# GPI.net
KiCad netlist of a schematic drawn in Altium Designer
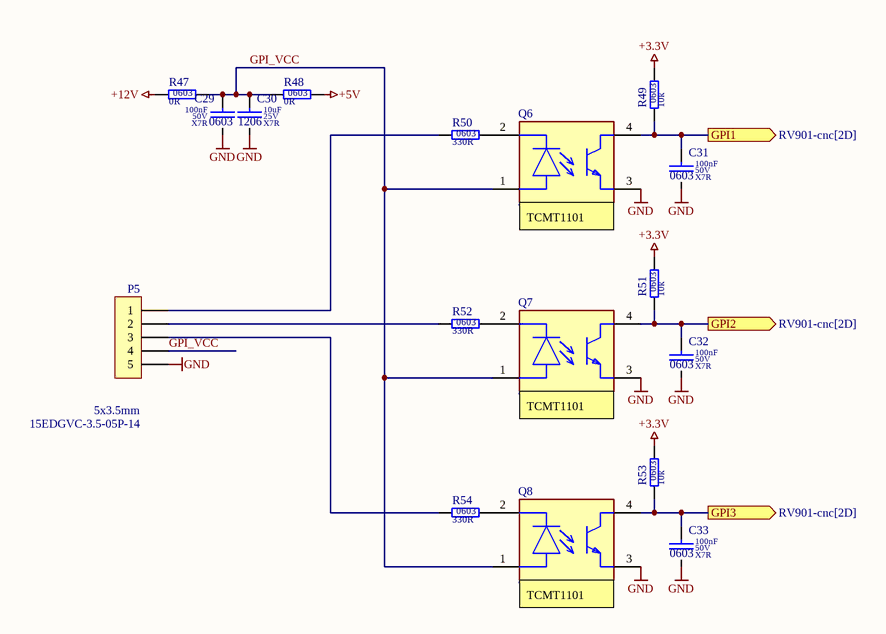
[diagram p0: GPI.SchDoc]

(export (version "E")
  (design (tool "Eeschema 10.0.6"))
  (components
    (comp (ref "C29")
      (value "100nF")
      (footprint "C_0603_1608")
      (description "Capacitor")
      (fields
        (field (name "DIELECTRIC") "X7R")
        (field (name "VOLTAGE") "50V")
        (field (name "SCH_FOOTPRINT") "0603")
        (field (name "PART NUMBER") "C_100nF_50V_X7R_0603_5")
        (field (name "MANUFACTURER") "Samsung")
      )
      (libsource (lib "Library") (part "C"))
    )
    (comp (ref "C30")
      (value "10uF")
      (footprint "C_1206_3216")
      (description "Capacitor")
      (fields
        (field (name "DIELECTRIC") "X7R")
        (field (name "VOLTAGE") "25V")
        (field (name "SCH_FOOTPRINT") "1206")
        (field (name "PART NUMBER") "C_10uF_25V_X7R_1206_10")
        (field (name "MANUFACTURER") "Samsung")
      )
      (libsource (lib "Library") (part "C"))
    )
    (comp (ref "C31")
      (value "100nF")
      (footprint "C_0603_1608")
      (description "Capacitor")
      (fields
        (field (name "DIELECTRIC") "X7R")
        (field (name "VOLTAGE") "50V")
        (field (name "SCH_FOOTPRINT") "0603")
        (field (name "PART NUMBER") "C_100nF_50V_X7R_0603_5")
        (field (name "MANUFACTURER") "Samsung")
      )
      (libsource (lib "Library") (part "C"))
    )
    (comp (ref "C32")
      (value "100nF")
      (footprint "C_0603_1608")
      (description "Capacitor")
      (fields
        (field (name "DIELECTRIC") "X7R")
        (field (name "VOLTAGE") "50V")
        (field (name "SCH_FOOTPRINT") "0603")
        (field (name "PART NUMBER") "C_100nF_50V_X7R_0603_5")
        (field (name "MANUFACTURER") "Samsung")
      )
      (libsource (lib "Library") (part "C"))
    )
    (comp (ref "C33")
      (value "100nF")
      (footprint "C_0603_1608")
      (description "Capacitor")
      (fields
        (field (name "DIELECTRIC") "X7R")
        (field (name "VOLTAGE") "50V")
        (field (name "SCH_FOOTPRINT") "0603")
        (field (name "PART NUMBER") "C_100nF_50V_X7R_0603_5")
        (field (name "MANUFACTURER") "Samsung")
      )
      (libsource (lib "Library") (part "C"))
    )
    (comp (ref "P5")
      (value "15EDGVC-3.5-05P-14")
      (footprint "P_15EDGVC-3.5-05P")
      (description "Pin Header")
      (fields
        (field (name "SCH_FOOTPRINT") "5x3.5mm")
        (field (name "PART NUMBER") "P_15EDGVC-3.5-05P-14")
        (field (name "MANUFACTURER") "DEGSON ELECTRONICS")
      )
      (libsource (lib "Library") (part "P_HEADER_1x5"))
    )
    (comp (ref "Q6")
      (value "TCMT1106")
      (footprint "FP-TCMT1106-MFG")
      (fields (field (name "VOLTAGE") "6V"))
      (libsource (lib "Altium Content Vault") (part "e07288ace2826ef443abdfb88e741da"))
    )
    (comp (ref "Q7")
      (value "TCMT1106")
      (footprint "FP-TCMT1106-MFG")
      (fields (field (name "VOLTAGE") "6V"))
      (libsource (lib "Altium Content Vault") (part "e07288ace2826ef443abdfb88e741da"))
    )
    (comp (ref "Q8")
      (value "TCMT1106")
      (footprint "FP-TCMT1106-MFG")
      (fields (field (name "VOLTAGE") "6V"))
      (libsource (lib "Altium Content Vault") (part "e07288ace2826ef443abdfb88e741da"))
    )
    (comp (ref "R47")
      (value "0R")
      (footprint "R_0603_1608")
      (fields
        (field (name "SCH_FOOTPRINT") "0603")
        (field (name "PART NUMBER") "R_0R_0603_1")
        (field (name "VOLTAGE") "75V")
        (field (name "POWER") "100mW")
      )
      (libsource (lib "Library") (part "R"))
    )
    (comp (ref "R48")
      (value "0R")
      (footprint "R_0603_1608")
      (fields
        (field (name "SCH_FOOTPRINT") "0603")
        (field (name "PART NUMBER") "R_0R_0603_1")
        (field (name "VOLTAGE") "75V")
        (field (name "POWER") "100mW")
      )
      (libsource (lib "Library") (part "R"))
    )
    (comp (ref "R49")
      (value "10k")
      (footprint "R_0603_1608")
      (fields
        (field (name "SCH_FOOTPRINT") "0603")
        (field (name "PART NUMBER") "R_10k_0603_1_AECQ0")
        (field (name "VOLTAGE") "75V")
        (field (name "POWER") "100mW")
      )
      (libsource (lib "Library") (part "R"))
    )
    (comp (ref "R50")
      (value "330R")
      (footprint "R_0603_1608")
      (fields
        (field (name "SCH_FOOTPRINT") "0603")
        (field (name "PART NUMBER") "R_330R_0603_1")
        (field (name "VOLTAGE") "50V")
        (field (name "POWER") "100mW")
      )
      (libsource (lib "Library") (part "R"))
    )
    (comp (ref "R51")
      (value "10k")
      (footprint "R_0603_1608")
      (fields
        (field (name "SCH_FOOTPRINT") "0603")
        (field (name "PART NUMBER") "R_10k_0603_1_AECQ0")
        (field (name "VOLTAGE") "75V")
        (field (name "POWER") "100mW")
      )
      (libsource (lib "Library") (part "R"))
    )
    (comp (ref "R52")
      (value "330R")
      (footprint "R_0603_1608")
      (fields
        (field (name "SCH_FOOTPRINT") "0603")
        (field (name "PART NUMBER") "R_330R_0603_1")
        (field (name "VOLTAGE") "50V")
        (field (name "POWER") "100mW")
      )
      (libsource (lib "Library") (part "R"))
    )
    (comp (ref "R53")
      (value "10k")
      (footprint "R_0603_1608")
      (fields
        (field (name "SCH_FOOTPRINT") "0603")
        (field (name "PART NUMBER") "R_10k_0603_1_AECQ0")
        (field (name "VOLTAGE") "75V")
        (field (name "POWER") "100mW")
      )
      (libsource (lib "Library") (part "R"))
    )
    (comp (ref "R54")
      (value "330R")
      (footprint "R_0603_1608")
      (fields
        (field (name "SCH_FOOTPRINT") "0603")
        (field (name "PART NUMBER") "R_330R_0603_1")
        (field (name "VOLTAGE") "50V")
        (field (name "POWER") "100mW")
      )
      (libsource (lib "Library") (part "R"))
    )
  )
  (nets
    (net (code "1") (name "+3.3V") (class "Default")
      (node (ref "R49") (pin "2") (pinfunction "2_2") (pintype "passive"))
      (node (ref "R51") (pin "2") (pinfunction "2_2") (pintype "passive"))
      (node (ref "R53") (pin "2") (pinfunction "2_2") (pintype "passive"))
    )
    (net (code "2") (name "+5V") (class "Default")
      (node (ref "R48") (pin "2") (pinfunction "2_2") (pintype "passive"))
    )
    (net (code "3") (name "+12V") (class "Default")
      (node (ref "R47") (pin "1") (pinfunction "1_1") (pintype "passive"))
    )
    (net (code "4") (name "/GPI1") (class "Default")
      (node (ref "C31") (pin "1") (pinfunction "1_1") (pintype "passive"))
      (node (ref "Q6") (pin "4") (pinfunction "C_4") (pintype "passive"))
      (node (ref "R49") (pin "1") (pinfunction "1_1") (pintype "passive"))
    )
    (net (code "5") (name "/GPI2") (class "Default")
      (node (ref "C32") (pin "1") (pinfunction "1_1") (pintype "passive"))
      (node (ref "Q7") (pin "4") (pinfunction "C_4") (pintype "passive"))
      (node (ref "R51") (pin "1") (pinfunction "1_1") (pintype "passive"))
    )
    (net (code "6") (name "/GPI3") (class "Default")
      (node (ref "C33") (pin "1") (pinfunction "1_1") (pintype "passive"))
      (node (ref "Q8") (pin "4") (pinfunction "C_4") (pintype "passive"))
      (node (ref "R53") (pin "1") (pinfunction "1_1") (pintype "passive"))
    )
    (net (code "7") (name "/GPI_VCC") (class "Default")
      (node (ref "C29") (pin "1") (pinfunction "1_1") (pintype "passive"))
      (node (ref "C30") (pin "1") (pinfunction "1_1") (pintype "passive"))
      (node (ref "P5") (pin "4") (pinfunction "4_4") (pintype "passive"))
      (node (ref "Q6") (pin "1") (pinfunction "A_1") (pintype "passive"))
      (node (ref "Q7") (pin "1") (pinfunction "A_1") (pintype "passive"))
      (node (ref "Q8") (pin "1") (pinfunction "A_1") (pintype "passive"))
      (node (ref "R47") (pin "2") (pinfunction "2_2") (pintype "passive"))
      (node (ref "R48") (pin "1") (pinfunction "1_1") (pintype "passive"))
    )
    (net (code "8") (name "GND") (class "Default")
      (node (ref "C29") (pin "2") (pinfunction "2_2") (pintype "passive"))
      (node (ref "C30") (pin "2") (pinfunction "2_2") (pintype "passive"))
      (node (ref "C31") (pin "2") (pinfunction "2_2") (pintype "passive"))
      (node (ref "C32") (pin "2") (pinfunction "2_2") (pintype "passive"))
      (node (ref "C33") (pin "2") (pinfunction "2_2") (pintype "passive"))
      (node (ref "P5") (pin "5") (pinfunction "5_5") (pintype "passive"))
      (node (ref "Q6") (pin "3") (pinfunction "E_3") (pintype "passive"))
      (node (ref "Q7") (pin "3") (pinfunction "E_3") (pintype "passive"))
      (node (ref "Q8") (pin "3") (pinfunction "E_3") (pintype "passive"))
    )
    (net (code "9") (name "Net-(P5-Pad1)") (class "Default")
      (node (ref "P5") (pin "1") (pinfunction "1_1") (pintype "passive"))
      (node (ref "R50") (pin "1") (pinfunction "1_1") (pintype "passive"))
    )
    (net (code "10") (name "Net-(P5-Pad2)") (class "Default")
      (node (ref "P5") (pin "2") (pinfunction "2_2") (pintype "passive"))
      (node (ref "R52") (pin "1") (pinfunction "1_1") (pintype "passive"))
    )
    (net (code "11") (name "Net-(P5-Pad3)") (class "Default")
      (node (ref "P5") (pin "3") (pinfunction "3_3") (pintype "passive"))
      (node (ref "R54") (pin "1") (pinfunction "1_1") (pintype "passive"))
    )
    (net (code "12") (name "Net-(Q6-C-Pad2)") (class "Default")
      (node (ref "Q6") (pin "2") (pinfunction "C_2") (pintype "passive"))
      (node (ref "R50") (pin "2") (pinfunction "2_2") (pintype "passive"))
    )
    (net (code "13") (name "Net-(Q7-C-Pad2)") (class "Default")
      (node (ref "Q7") (pin "2") (pinfunction "C_2") (pintype "passive"))
      (node (ref "R52") (pin "2") (pinfunction "2_2") (pintype "passive"))
    )
    (net (code "14") (name "Net-(Q8-C-Pad2)") (class "Default")
      (node (ref "Q8") (pin "2") (pinfunction "C_2") (pintype "passive"))
      (node (ref "R54") (pin "2") (pinfunction "2_2") (pintype "passive"))
    )
  )
)
